# Placa_ADA.net
KiCad netlist of a schematic drawn in Altium Designer
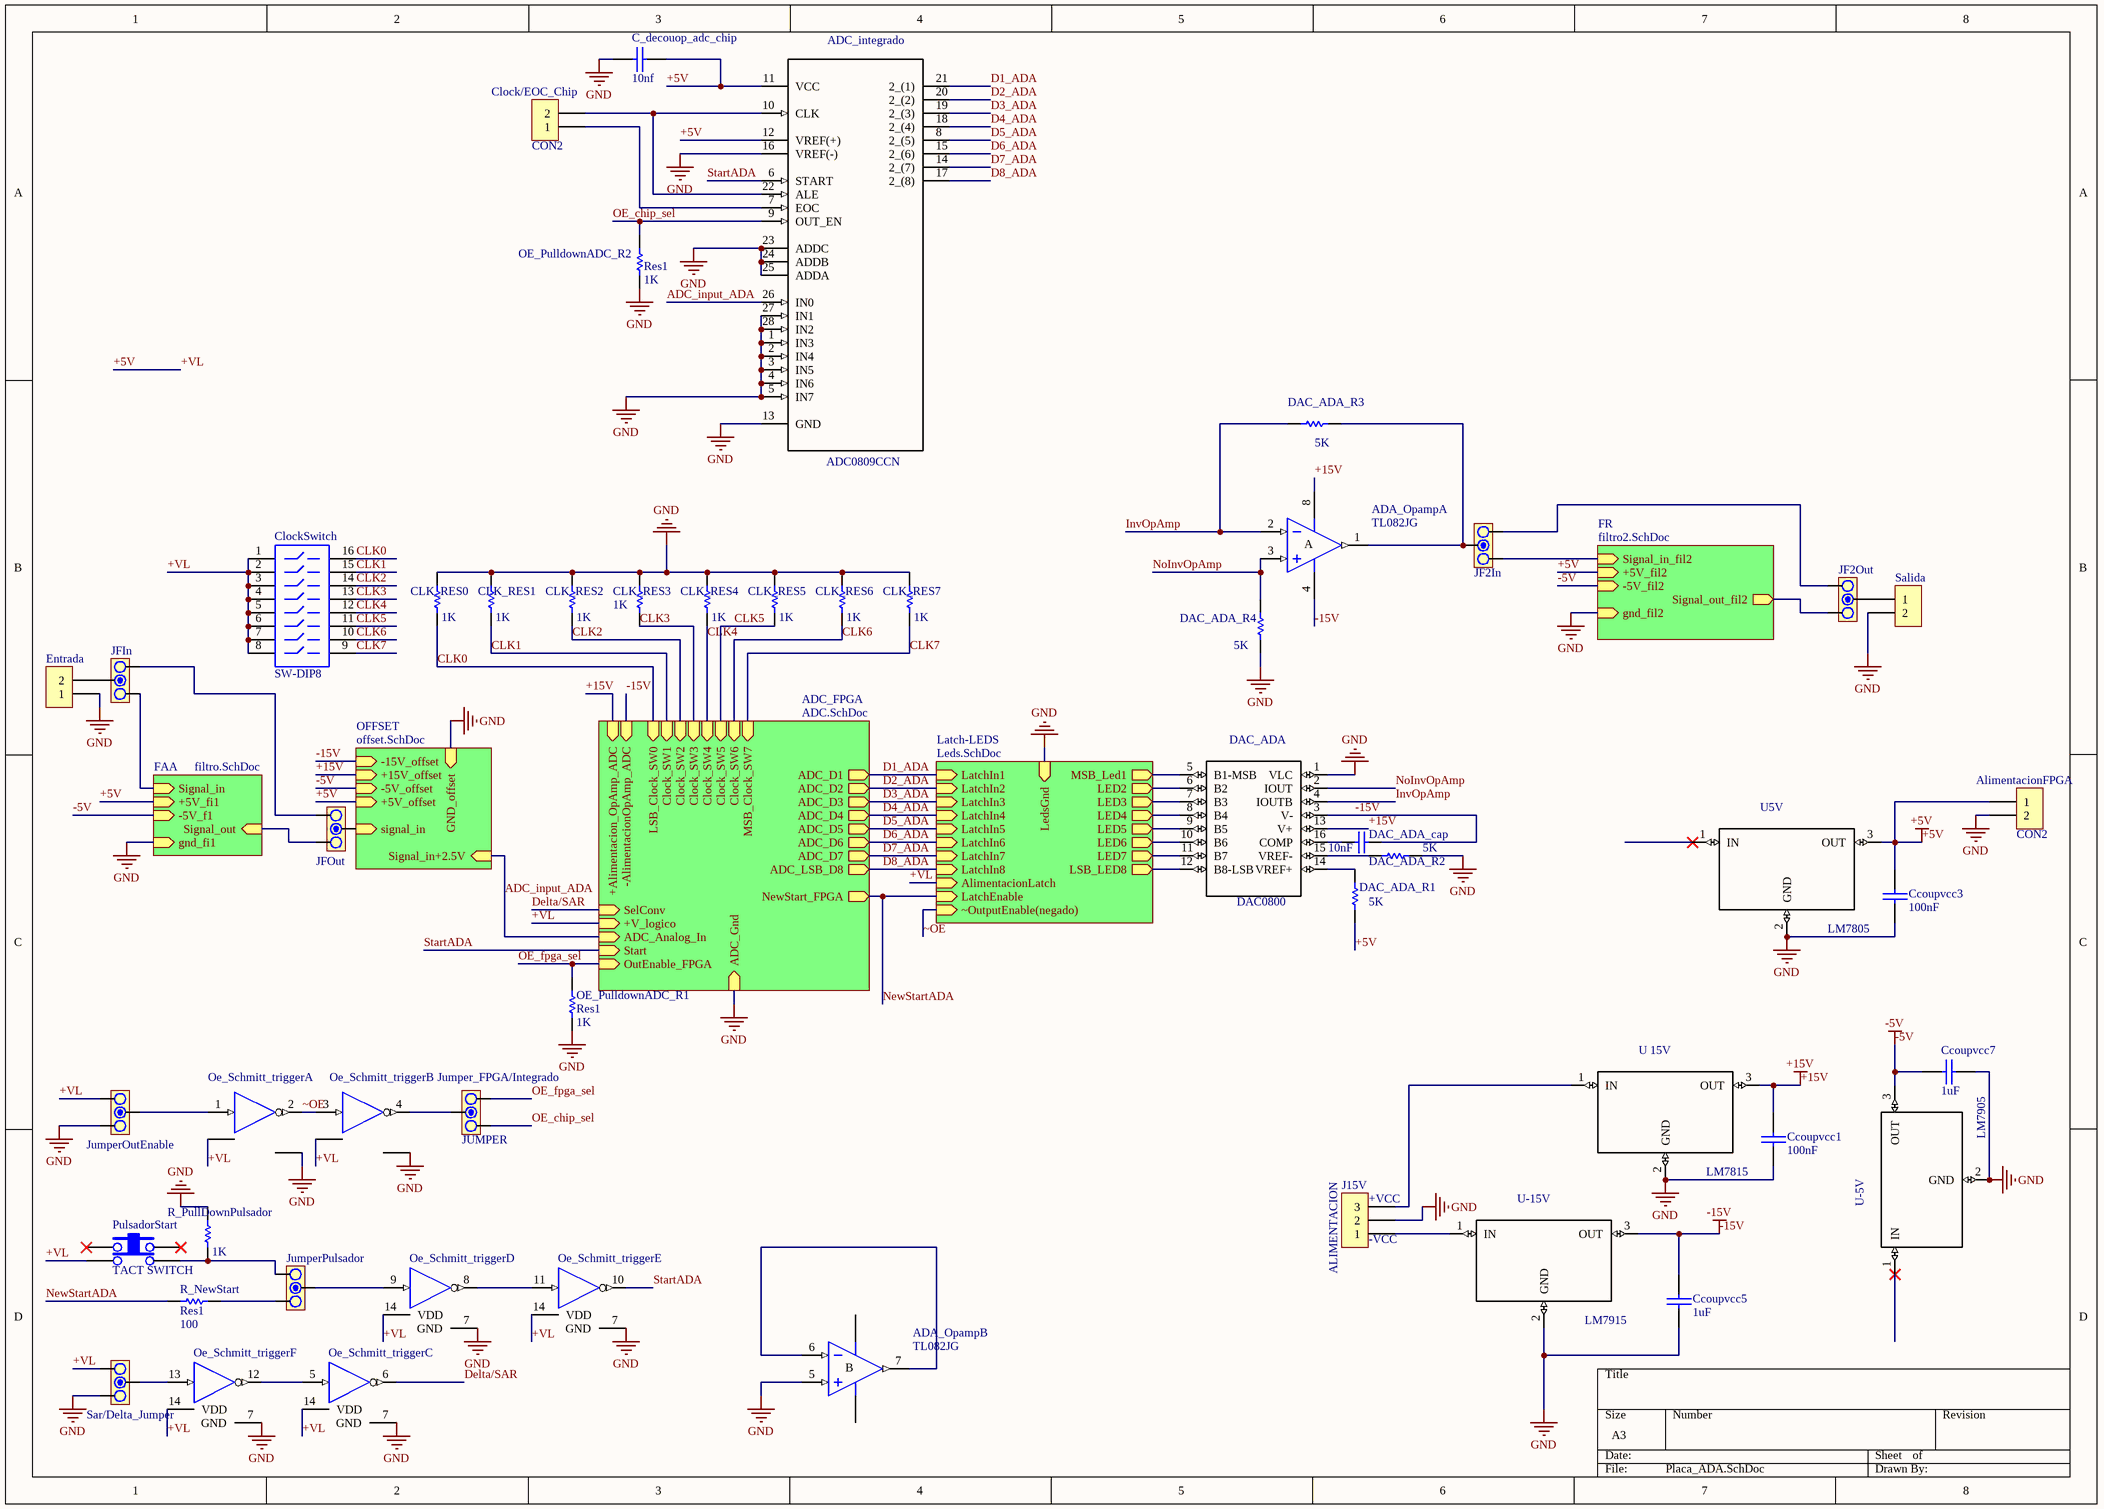
[diagram p0: Placa_ADA.SchDoc]

(export (version "E")
  (design (tool "Eeschema 10.0.6"))
  (components
    (comp (ref "ADA_Opamp")
      (value "TL082JG")
      (footprint "JG008")
      (description "JFET-Input Operational Amplifier")
      (fields (field (name "PUBLISHER") "Altium Limited"))
      (libsource (lib "TI Operational Amplifier") (part "TL082JG"))
    )
    (comp (ref "ADC_integrado")
      (value "ADC0809CCN")
      (footprint "*DIP254P1524X483-28")
      (description "8-bit Microprocessor Compatible A/D Converters With 8-Channel Multiplexer 28-PDIP -40 to 85")
      (fields (field (name "MP") "ADC0809CCN/NOPB") (field (name "MF") "Texas Instruments"))
      (libsource (lib "ADC0809CCN") (part "ADC0809CCN"))
    )
    (comp (ref "AlimentacionFPGA")
      (value "CON2")
      (footprint "SIP2")
      (libsource (lib "LIBEBAL") (part "CON2"))
    )
    (comp (ref "Ccoupvcc1") (value "100nF") (footprint "CAP200") (libsource (lib "LIBEBAL") (part "CAP")))
    (comp (ref "Ccoupvcc3") (value "100nF") (footprint "CAP200") (libsource (lib "LIBEBAL") (part "CAP")))
    (comp (ref "Ccoupvcc5") (value "1uF") (footprint "CAP200") (libsource (lib "LIBEBAL") (part "CAP")))
    (comp (ref "Ccoupvcc7") (value "1uF") (footprint "CAP200") (libsource (lib "LIBEBAL") (part "CAP")))
    (comp (ref "CLK_RES0")
      (value "1K")
      (footprint "AXIAL-0.3")
      (description "Resistor")
      (fields (field (name "Comment") "Res1") (field (name "PUBLISHER") "Altium Limited"))
      (libsource (lib "Miscellaneous Devices") (part "Res1"))
    )
    (comp (ref "CLK_RES1")
      (value "1K")
      (footprint "AXIAL-0.3")
      (description "Resistor")
      (fields (field (name "Comment") "Res1") (field (name "PUBLISHER") "Altium Limited"))
      (libsource (lib "Miscellaneous Devices") (part "Res1"))
    )
    (comp (ref "CLK_RES2")
      (value "1K")
      (footprint "AXIAL-0.3")
      (description "Resistor")
      (fields (field (name "Comment") "Res1") (field (name "PUBLISHER") "Altium Limited"))
      (libsource (lib "Miscellaneous Devices") (part "Res1"))
    )
    (comp (ref "CLK_RES3")
      (value "1K")
      (footprint "AXIAL-0.3")
      (description "Resistor")
      (fields (field (name "Comment") "Res1") (field (name "PUBLISHER") "Altium Limited"))
      (libsource (lib "Miscellaneous Devices") (part "Res1"))
    )
    (comp (ref "CLK_RES4")
      (value "1K")
      (footprint "AXIAL-0.3")
      (description "Resistor")
      (fields (field (name "Comment") "Res1") (field (name "PUBLISHER") "Altium Limited"))
      (libsource (lib "Miscellaneous Devices") (part "Res1"))
    )
    (comp (ref "CLK_RES5")
      (value "1K")
      (footprint "AXIAL-0.3")
      (description "Resistor")
      (fields (field (name "Comment") "Res1") (field (name "PUBLISHER") "Altium Limited"))
      (libsource (lib "Miscellaneous Devices") (part "Res1"))
    )
    (comp (ref "CLK_RES6")
      (value "1K")
      (footprint "AXIAL-0.3")
      (description "Resistor")
      (fields (field (name "Comment") "Res1") (field (name "PUBLISHER") "Altium Limited"))
      (libsource (lib "Miscellaneous Devices") (part "Res1"))
    )
    (comp (ref "CLK_RES7")
      (value "1K")
      (footprint "AXIAL-0.3")
      (description "Resistor")
      (fields (field (name "Comment") "Res1") (field (name "PUBLISHER") "Altium Limited"))
      (libsource (lib "Miscellaneous Devices") (part "Res1"))
    )
    (comp (ref "Clock/EOC_Chip") (value "CON2") (footprint "SIP2") (libsource (lib "") (part "CON2_1")))
    (comp (ref "ClockSwitch")
      (value "SW-DIP8")
      (footprint "DIP-16-KEY")
      (description "4009 Series DIP Switch, Raised actuator")
      (fields (field (name "PUBLISHER") "Altium Limited"))
      (libsource (lib "Miscellaneous Devices") (part "SW-DIP8"))
    )
    (comp (ref "C_decouop_adc_chip")
      (value "10nf")
      (footprint "CAP200")
      (libsource (lib "LIBEBAL") (part "CAP"))
    )
    (comp (ref "DAC_ADA")
      (value "DAC0800")
      (footprint "*DIL16")
      (fields
        (field (name "MF") "Texas Instruments")
        (field (name "DIGI-KEY_PART_NUMBER") "DAC0800LCN/NOPB-ND")
      )
      (libsource (lib "DAC0800") (part "DAC0800"))
    )
    (comp (ref "DAC_ADA_cap")
      (value "10nF")
      (footprint "RAD-0.3")
      (description "Capacitor")
      (fields (field (name "Comment") "Cap") (field (name "PUBLISHER") "Altium Limited"))
      (libsource (lib "Miscellaneous Devices") (part "Cap"))
    )
    (comp (ref "DAC_ADA_R1")
      (value "5K")
      (footprint "AXIAL-0.3")
      (description "Resistor")
      (fields (field (name "Comment") "Res1") (field (name "PUBLISHER") "Altium Limited"))
      (libsource (lib "Miscellaneous Devices") (part "Res1"))
    )
    (comp (ref "DAC_ADA_R2")
      (value "5K")
      (footprint "AXIAL-0.3")
      (description "Resistor")
      (fields (field (name "Comment") "Res1") (field (name "PUBLISHER") "Altium Limited"))
      (libsource (lib "Miscellaneous Devices") (part "Res1"))
    )
    (comp (ref "DAC_ADA_R3")
      (value "5K")
      (footprint "AXIAL-0.3")
      (description "Resistor")
      (fields (field (name "Comment") "Res1") (field (name "PUBLISHER") "Altium Limited"))
      (libsource (lib "Miscellaneous Devices") (part "Res1"))
    )
    (comp (ref "DAC_ADA_R4")
      (value "5K")
      (footprint "AXIAL-0.3")
      (description "Resistor")
      (fields (field (name "Comment") "Res1") (field (name "PUBLISHER") "Altium Limited"))
      (libsource (lib "Miscellaneous Devices") (part "Res1"))
    )
    (comp (ref "Entrada")
      (value "BORNERA 2")
      (footprint "BORNERA2")
      (libsource (lib "LIBEBAL") (part "BORNERA 2"))
    )
    (comp (ref "J15V")
      (value "ALIMENTACION")
      (footprint "BORNERA3")
      (libsource (lib "LIBEBAL") (part "BORNERA 3"))
    )
    (comp (ref "JF2In") (value "JUMPER") (footprint "JUMPER3") (libsource (lib "") (part "JUMPER3_1")))
    (comp (ref "JF2Out") (value "JUMPER") (footprint "JUMPER3") (libsource (lib "LIBEBAL") (part "JUMPER3")))
    (comp (ref "JFIn") (value "JUMPER") (footprint "JUMPER3") (libsource (lib "") (part "JUMPER3_1")))
    (comp (ref "JFOut") (value "JUMPER") (footprint "JUMPER3") (libsource (lib "LIBEBAL") (part "JUMPER3")))
    (comp (ref "JumperOutEnable")
      (value "JUMPER")
      (footprint "JUMPER3")
      (libsource (lib "LIBEBAL") (part "JUMPER3"))
    )
    (comp (ref "JumperPulsador")
      (value "JUMPER")
      (footprint "JUMPER3")
      (libsource (lib "LIBEBAL") (part "JUMPER3"))
    )
    (comp (ref "Jumper_FPGA/Integrado")
      (value "JUMPER")
      (footprint "JUMPER3")
      (libsource (lib "") (part "JUMPER3_1"))
    )
    (comp (ref "OE_PulldownADC_R1")
      (value "Res1")
      (footprint "AXIAL-0.3")
      (description "Resistor")
      (fields (field (name "ALTIUM_VALUE") "1K") (field (name "PUBLISHER") "Altium Limited"))
      (libsource (lib "Miscellaneous Devices") (part "Res1"))
    )
    (comp (ref "OE_PulldownADC_R2")
      (value "Res1")
      (footprint "AXIAL-0.3")
      (description "Resistor")
      (fields (field (name "ALTIUM_VALUE") "1K") (field (name "PUBLISHER") "Altium Limited"))
      (libsource (lib "Miscellaneous Devices") (part "Res1"))
    )
    (comp (ref "Oe_Schmitt_trigger")
      (value "MC74HC14AN")
      (footprint "646-06")
      (description "Hex Schmitt-Trigger Inverter")
      (fields (field (name "PUBLISHER") "Altium Limited"))
      (libsource (lib "ON Semi Logic Buffer Line Driver") (part "MC74HC14AN"))
    )
    (comp (ref "PulsadorStart")
      (value "TACT SWITCH")
      (footprint "TACTSWITCH")
      (libsource (lib "LIBEBAL") (part "TACT SWITCH"))
    )
    (comp (ref "R_NewStart")
      (value "Res1")
      (footprint "AXIAL-0.3")
      (description "Resistor")
      (fields (field (name "ALTIUM_VALUE") "100") (field (name "PUBLISHER") "Altium Limited"))
      (libsource (lib "Miscellaneous Devices") (part "Res1"))
    )
    (comp (ref "R_PullDownPulsador")
      (value "1K")
      (footprint "AXIAL-0.3")
      (description "Resistor")
      (fields (field (name "Comment") "Res1") (field (name "PUBLISHER") "Altium Limited"))
      (libsource (lib "Miscellaneous Devices") (part "Res1"))
    )
    (comp (ref "Salida") (value "BORNERA 2") (footprint "BORNERA2") (libsource (lib "") (part "BORNERA 2_1")))
    (comp (ref "Sar/Delta_Jumper")
      (value "JUMPER")
      (footprint "JUMPER3")
      (libsource (lib "LIBEBAL") (part "JUMPER3"))
    )
    (comp (ref "U 15V")
      (value "LM7815")
      (footprint "*TO220")
      (fields (field (name "MP") "LM7805") (field (name "MF") "Texas Instruments"))
      (libsource (lib "LM7805") (part "LM7805"))
    )
    (comp (ref "U-5V")
      (value "LM7905")
      (footprint "*TO220")
      (fields (field (name "MP") "LM7805") (field (name "MF") "Texas Instruments"))
      (libsource (lib "LM7805") (part "LM7805"))
    )
    (comp (ref "U-15V")
      (value "LM7915")
      (footprint "*TO220")
      (fields (field (name "MP") "LM7805") (field (name "MF") "Texas Instruments"))
      (libsource (lib "LM7805") (part "LM7805"))
    )
    (comp (ref "U5V")
      (value "LM7805")
      (footprint "*TO220")
      (fields (field (name "MF") "Texas Instruments"))
      (libsource (lib "LM7805") (part "LM7805"))
    )
  )
  (nets
    (net (code "1") (name "+5V") (class "Default")
      (node (ref "ADC_integrado") (pin "11") (pinfunction "VCC_11") (pintype "power_in"))
      (node (ref "ADC_integrado") (pin "12") (pinfunction "VREF(+)_12") (pintype "passive"))
      (node (ref "AlimentacionFPGA") (pin "1") (pinfunction "1_1") (pintype "passive"))
      (node (ref "C_decouop_adc_chip") (pin "2") (pinfunction "2_2") (pintype "passive"))
      (node (ref "Ccoupvcc3") (pin "1") (pinfunction "1_1") (pintype "passive"))
      (node (ref "ClockSwitch") (pin "1") (pinfunction "1_1") (pintype "passive"))
      (node (ref "ClockSwitch") (pin "2") (pinfunction "2_2") (pintype "passive"))
      (node (ref "ClockSwitch") (pin "3") (pinfunction "3_3") (pintype "passive"))
      (node (ref "ClockSwitch") (pin "4") (pinfunction "4_4") (pintype "passive"))
      (node (ref "ClockSwitch") (pin "5") (pinfunction "5_5") (pintype "passive"))
      (node (ref "ClockSwitch") (pin "6") (pinfunction "6_6") (pintype "passive"))
      (node (ref "ClockSwitch") (pin "7") (pinfunction "7_7") (pintype "passive"))
      (node (ref "ClockSwitch") (pin "8") (pinfunction "8_8") (pintype "passive"))
      (node (ref "DAC_ADA_R1") (pin "1") (pinfunction "1_1") (pintype "passive"))
      (node (ref "JumperOutEnable") (pin "3") (pinfunction "3_3") (pintype "passive"))
      (node (ref "Oe_Schmitt_trigger") (pin "14") (pinfunction "VDD_14") (pintype "power_in"))
      (node (ref "PulsadorStart") (pin "2") (pinfunction "2_2") (pintype "passive"))
      (node (ref "Sar/Delta_Jumper") (pin "3") (pinfunction "3_3") (pintype "passive"))
      (node (ref "U5V") (pin "3") (pinfunction "OUT_3") (pintype "bidirectional"))
    )
    (net (code "2") (name "+15V") (class "Default")
      (node (ref "ADA_Opamp") (pin "8") (pinfunction "V+_8") (pintype "power_in"))
      (node (ref "Ccoupvcc1") (pin "1") (pinfunction "1_1") (pintype "passive"))
      (node (ref "DAC_ADA") (pin "13") (pinfunction "V+_13") (pintype "bidirectional"))
      (node (ref "U 15V") (pin "3") (pinfunction "OUT_3") (pintype "bidirectional"))
    )
    (net (code "3") (name "-5V") (class "Default")
      (node (ref "Ccoupvcc7") (pin "1") (pinfunction "1_1") (pintype "passive"))
      (node (ref "U-5V") (pin "3") (pinfunction "OUT_3") (pintype "bidirectional"))
    )
    (net (code "4") (name "-15V") (class "Default")
      (node (ref "ADA_Opamp") (pin "4") (pinfunction "V-_4") (pintype "power_in"))
      (node (ref "Ccoupvcc5") (pin "1") (pinfunction "1_1") (pintype "passive"))
      (node (ref "DAC_ADA") (pin "3") (pinfunction "V-_3") (pintype "bidirectional"))
      (node (ref "DAC_ADA_cap") (pin "2") (pinfunction "2_2") (pintype "passive"))
      (node (ref "U-15V") (pin "3") (pinfunction "OUT_3") (pintype "bidirectional"))
    )
    (net (code "5") (name "/ADC_input_ADA") (class "Default")
      (node (ref "ADC_integrado") (pin "26") (pinfunction "IN0_26") (pintype "input"))
    )
    (net (code "6") (name "/CLK0") (class "Default")
      (node (ref "CLK_RES0") (pin "1") (pinfunction "1_1") (pintype "passive"))
      (node (ref "ClockSwitch") (pin "16") (pinfunction "16_16") (pintype "passive"))
    )
    (net (code "7") (name "/CLK1") (class "Default")
      (node (ref "CLK_RES1") (pin "1") (pinfunction "1_1") (pintype "passive"))
      (node (ref "ClockSwitch") (pin "15") (pinfunction "15_15") (pintype "passive"))
    )
    (net (code "8") (name "/CLK2") (class "Default")
      (node (ref "CLK_RES2") (pin "1") (pinfunction "1_1") (pintype "passive"))
      (node (ref "ClockSwitch") (pin "14") (pinfunction "14_14") (pintype "passive"))
    )
    (net (code "9") (name "/CLK3") (class "Default")
      (node (ref "CLK_RES3") (pin "1") (pinfunction "1_1") (pintype "passive"))
      (node (ref "ClockSwitch") (pin "13") (pinfunction "13_13") (pintype "passive"))
    )
    (net (code "10") (name "/CLK4") (class "Default")
      (node (ref "CLK_RES4") (pin "1") (pinfunction "1_1") (pintype "passive"))
      (node (ref "ClockSwitch") (pin "12") (pinfunction "12_12") (pintype "passive"))
    )
    (net (code "11") (name "/CLK5") (class "Default")
      (node (ref "CLK_RES5") (pin "1") (pinfunction "1_1") (pintype "passive"))
      (node (ref "ClockSwitch") (pin "11") (pinfunction "11_11") (pintype "passive"))
    )
    (net (code "12") (name "/CLK6") (class "Default")
      (node (ref "CLK_RES6") (pin "1") (pinfunction "1_1") (pintype "passive"))
      (node (ref "ClockSwitch") (pin "10") (pinfunction "10_10") (pintype "passive"))
    )
    (net (code "13") (name "/CLK7") (class "Default")
      (node (ref "CLK_RES7") (pin "1") (pinfunction "1_1") (pintype "passive"))
      (node (ref "ClockSwitch") (pin "9") (pinfunction "9_9") (pintype "passive"))
    )
    (net (code "14") (name "/D1_ADA") (class "Default")
      (node (ref "ADC_integrado") (pin "21") (pinfunction "2_(1)_21") (pintype "passive"))
    )
    (net (code "15") (name "/D2_ADA") (class "Default")
      (node (ref "ADC_integrado") (pin "20") (pinfunction "2_(2)_20") (pintype "passive"))
    )
    (net (code "16") (name "/D3_ADA") (class "Default")
      (node (ref "ADC_integrado") (pin "19") (pinfunction "2_(3)_19") (pintype "passive"))
    )
    (net (code "17") (name "/D4_ADA") (class "Default")
      (node (ref "ADC_integrado") (pin "18") (pinfunction "2_(4)_18") (pintype "passive"))
    )
    (net (code "18") (name "/D5_ADA") (class "Default")
      (node (ref "ADC_integrado") (pin "8") (pinfunction "2_(5)_8") (pintype "passive"))
    )
    (net (code "19") (name "/D6_ADA") (class "Default")
      (node (ref "ADC_integrado") (pin "15") (pinfunction "2_(6)_15") (pintype "passive"))
    )
    (net (code "20") (name "/D7_ADA") (class "Default")
      (node (ref "ADC_integrado") (pin "14") (pinfunction "2_(7)_14") (pintype "passive"))
    )
    (net (code "21") (name "/D8_ADA") (class "Default")
      (node (ref "ADC_integrado") (pin "17") (pinfunction "2_(8)_17") (pintype "passive"))
    )
    (net (code "22") (name "/Delta{slash}SAR") (class "Default")
      (node (ref "Oe_Schmitt_trigger") (pin "6") (pinfunction "~{OUT}_6") (pintype "output"))
    )
    (net (code "23") (name "/InvOpAmp") (class "Default")
      (node (ref "ADA_Opamp") (pin "2") (pinfunction "IN-_2") (pintype "input"))
      (node (ref "DAC_ADA") (pin "4") (pinfunction "IOUTB_4") (pintype "bidirectional"))
      (node (ref "DAC_ADA_R3") (pin "1") (pinfunction "1_1") (pintype "passive"))
    )
    (net (code "24") (name "/LED2") (class "Default")
      (node (ref "DAC_ADA") (pin "6") (pinfunction "B2_6") (pintype "bidirectional"))
    )
    (net (code "25") (name "/LED3") (class "Default")
      (node (ref "DAC_ADA") (pin "7") (pinfunction "B3_7") (pintype "bidirectional"))
    )
    (net (code "26") (name "/LED4") (class "Default")
      (node (ref "DAC_ADA") (pin "8") (pinfunction "B4_8") (pintype "bidirectional"))
    )
    (net (code "27") (name "/LED5") (class "Default")
      (node (ref "DAC_ADA") (pin "9") (pinfunction "B5_9") (pintype "bidirectional"))
    )
    (net (code "28") (name "/LED6") (class "Default")
      (node (ref "DAC_ADA") (pin "10") (pinfunction "B6_10") (pintype "bidirectional"))
    )
    (net (code "29") (name "/LED7") (class "Default")
      (node (ref "DAC_ADA") (pin "11") (pinfunction "B7_11") (pintype "bidirectional"))
    )
    (net (code "30") (name "/LSB_LED8") (class "Default")
      (node (ref "DAC_ADA") (pin "12") (pinfunction "B8-LSB_12") (pintype "bidirectional"))
    )
    (net (code "31") (name "/MSB_Led1") (class "Default")
      (node (ref "DAC_ADA") (pin "5") (pinfunction "B1-MSB_5") (pintype "bidirectional"))
    )
    (net (code "32") (name "/NewStartADA") (class "Default")
      (node (ref "R_NewStart") (pin "1") (pinfunction "1_1") (pintype "passive"))
    )
    (net (code "33") (name "/NoInvOpAmp") (class "Default")
      (node (ref "ADA_Opamp") (pin "3") (pinfunction "IN+_3") (pintype "input"))
      (node (ref "DAC_ADA") (pin "2") (pinfunction "IOUT_2") (pintype "bidirectional"))
      (node (ref "DAC_ADA_R4") (pin "2") (pinfunction "2_2") (pintype "passive"))
    )
    (net (code "34") (name "/OE_chip_sel") (class "Default")
      (node (ref "ADC_integrado") (pin "9") (pinfunction "OUT_EN_9") (pintype "input"))
      (node (ref "Jumper_FPGA/Integrado") (pin "3") (pinfunction "3_3") (pintype "passive"))
      (node (ref "OE_PulldownADC_R2") (pin "2") (pinfunction "2_2") (pintype "passive"))
    )
    (net (code "35") (name "/OE_fpga_sel") (class "Default")
      (node (ref "Jumper_FPGA/Integrado") (pin "1") (pinfunction "1_1") (pintype "passive"))
      (node (ref "OE_PulldownADC_R1") (pin "2") (pinfunction "2_2") (pintype "passive"))
    )
    (net (code "36") (name "/Signal_in") (class "Default")
      (node (ref "JFIn") (pin "3") (pinfunction "3_3") (pintype "passive"))
    )
    (net (code "37") (name "/Signal_in_fil2") (class "Default")
      (node (ref "JF2In") (pin "3") (pinfunction "3_3") (pintype "passive"))
    )
    (net (code "38") (name "/Signal_out") (class "Default")
      (node (ref "JFOut") (pin "1") (pinfunction "1_1") (pintype "passive"))
    )
    (net (code "39") (name "/Signal_out_fil2") (class "Default")
      (node (ref "JF2Out") (pin "1") (pinfunction "1_1") (pintype "passive"))
    )
    (net (code "40") (name "/StartADA") (class "Default")
      (node (ref "ADC_integrado") (pin "6") (pinfunction "START_6") (pintype "input"))
      (node (ref "Oe_Schmitt_trigger") (pin "10") (pinfunction "~{OUT}_10") (pintype "output"))
    )
    (net (code "41") (name "/signal_in") (class "Default")
      (node (ref "JFOut") (pin "2") (pinfunction "2_2") (pintype "passive"))
    )
    (net (code "42") (name "/~OE") (class "Default")
      (node (ref "Oe_Schmitt_trigger") (pin "2") (pinfunction "~{OUT}_2") (pintype "output"))
      (node (ref "Oe_Schmitt_trigger") (pin "3") (pinfunction "IN_3") (pintype "input"))
    )
    (net (code "43") (name "GND") (class "Default")
      (node (ref "ADA_Opamp") (pin "5") (pinfunction "IN+_5") (pintype "input"))
      (node (ref "ADC_integrado") (pin "1") (pinfunction "IN3_1") (pintype "input"))
      (node (ref "ADC_integrado") (pin "13") (pinfunction "GND_13") (pintype "passive"))
      (node (ref "ADC_integrado") (pin "16") (pinfunction "VREF(-)_16") (pintype "passive"))
      (node (ref "ADC_integrado") (pin "2") (pinfunction "IN4_2") (pintype "input"))
      (node (ref "ADC_integrado") (pin "23") (pinfunction "ADDC_23") (pintype "passive"))
      (node (ref "ADC_integrado") (pin "24") (pinfunction "ADDB_24") (pintype "passive"))
      (node (ref "ADC_integrado") (pin "25") (pinfunction "ADDA_25") (pintype "passive"))
      (node (ref "ADC_integrado") (pin "27") (pinfunction "IN1_27") (pintype "input"))
      (node (ref "ADC_integrado") (pin "28") (pinfunction "IN2_28") (pintype "input"))
      (node (ref "ADC_integrado") (pin "3") (pinfunction "IN5_3") (pintype "input"))
      (node (ref "ADC_integrado") (pin "4") (pinfunction "IN6_4") (pintype "input"))
      (node (ref "ADC_integrado") (pin "5") (pinfunction "IN7_5") (pintype "input"))
      (node (ref "AlimentacionFPGA") (pin "2") (pinfunction "2_2") (pintype "passive"))
      (node (ref "CLK_RES0") (pin "2") (pinfunction "2_2") (pintype "passive"))
      (node (ref "CLK_RES1") (pin "2") (pinfunction "2_2") (pintype "passive"))
      (node (ref "CLK_RES2") (pin "2") (pinfunction "2_2") (pintype "passive"))
      (node (ref "CLK_RES3") (pin "2") (pinfunction "2_2") (pintype "passive"))
      (node (ref "CLK_RES4") (pin "2") (pinfunction "2_2") (pintype "passive"))
      (node (ref "CLK_RES5") (pin "2") (pinfunction "2_2") (pintype "passive"))
      (node (ref "CLK_RES6") (pin "2") (pinfunction "2_2") (pintype "passive"))
      (node (ref "CLK_RES7") (pin "2") (pinfunction "2_2") (pintype "passive"))
      (node (ref "C_decouop_adc_chip") (pin "1") (pinfunction "1_1") (pintype "passive"))
      (node (ref "Ccoupvcc1") (pin "2") (pinfunction "2_2") (pintype "passive"))
      (node (ref "Ccoupvcc3") (pin "2") (pinfunction "2_2") (pintype "passive"))
      (node (ref "Ccoupvcc5") (pin "2") (pinfunction "2_2") (pintype "passive"))
      (node (ref "Ccoupvcc7") (pin "2") (pinfunction "2_2") (pintype "passive"))
      (node (ref "DAC_ADA") (pin "1") (pinfunction "VLC_1") (pintype "bidirectional"))
      (node (ref "DAC_ADA_R2") (pin "2") (pinfunction "2_2") (pintype "passive"))
      (node (ref "DAC_ADA_R4") (pin "1") (pinfunction "1_1") (pintype "passive"))
      (node (ref "Entrada") (pin "1") (pinfunction "1_1") (pintype "passive"))
      (node (ref "J15V") (pin "2") (pinfunction "2_2") (pintype "passive"))
      (node (ref "JumperOutEnable") (pin "1") (pinfunction "1_1") (pintype "passive"))
      (node (ref "OE_PulldownADC_R1") (pin "1") (pinfunction "1_1") (pintype "passive"))
      (node (ref "OE_PulldownADC_R2") (pin "1") (pinfunction "1_1") (pintype "passive"))
      (node (ref "Oe_Schmitt_trigger") (pin "7") (pinfunction "GND_7") (pintype "power_in"))
      (node (ref "R_PullDownPulsador") (pin "2") (pinfunction "2_2") (pintype "passive"))
      (node (ref "Salida") (pin "2") (pinfunction "2_2") (pintype "passive"))
      (node (ref "Sar/Delta_Jumper") (pin "1") (pinfunction "1_1") (pintype "passive"))
      (node (ref "U 15V") (pin "2") (pinfunction "GND_2") (pintype "bidirectional"))
      (node (ref "U-15V") (pin "2") (pinfunction "GND_2") (pintype "bidirectional"))
      (node (ref "U-5V") (pin "2") (pinfunction "GND_2") (pintype "bidirectional"))
      (node (ref "U5V") (pin "2") (pinfunction "GND_2") (pintype "bidirectional"))
    )
    (net (code "44") (name "Net-(ADA_OpampA-OUT)") (class "Default")
      (node (ref "ADA_Opamp") (pin "1") (pinfunction "OUT_1") (pintype "output"))
      (node (ref "DAC_ADA_R3") (pin "2") (pinfunction "2_2") (pintype "passive"))
      (node (ref "JF2In") (pin "2") (pinfunction "2_2") (pintype "passive"))
    )
    (net (code "45") (name "Net-(ADA_OpampB-IN-)") (class "Default")
      (node (ref "ADA_Opamp") (pin "6") (pinfunction "IN-_6") (pintype "input"))
      (node (ref "ADA_Opamp") (pin "7") (pinfunction "OUT_7") (pintype "output"))
    )
    (net (code "46") (name "Net-(ADC_integrado-ALE)") (class "Default")
      (node (ref "ADC_integrado") (pin "10") (pinfunction "CLK_10") (pintype "input"))
      (node (ref "ADC_integrado") (pin "22") (pinfunction "ALE_22") (pintype "input"))
      (node (ref "Clock/EOC_Chip") (pin "2") (pinfunction "2_2") (pintype "passive"))
    )
    (net (code "47") (name "Net-(ADC_integrado-EOC)") (class "Default")
      (node (ref "ADC_integrado") (pin "7") (pinfunction "EOC_7") (pintype "input"))
      (node (ref "Clock/EOC_Chip") (pin "1") (pinfunction "1_1") (pintype "passive"))
    )
    (net (code "48") (name "Net-(DAC_ADA-COMP)") (class "Default")
      (node (ref "DAC_ADA") (pin "16") (pinfunction "COMP_16") (pintype "bidirectional"))
      (node (ref "DAC_ADA_cap") (pin "1") (pinfunction "1_1") (pintype "passive"))
    )
    (net (code "49") (name "Net-(DAC_ADA-VREF+)") (class "Default")
      (node (ref "DAC_ADA") (pin "14") (pinfunction "VREF+_14") (pintype "bidirectional"))
      (node (ref "DAC_ADA_R1") (pin "2") (pinfunction "2_2") (pintype "passive"))
    )
    (net (code "50") (name "Net-(DAC_ADA-VREF-)") (class "Default")
      (node (ref "DAC_ADA") (pin "15") (pinfunction "VREF-_15") (pintype "bidirectional"))
      (node (ref "DAC_ADA_R2") (pin "1") (pinfunction "1_1") (pintype "passive"))
    )
    (net (code "51") (name "Net-(Entrada-Pad2)") (class "Default")
      (node (ref "Entrada") (pin "2") (pinfunction "2_2") (pintype "passive"))
      (node (ref "JFIn") (pin "2") (pinfunction "2_2") (pintype "passive"))
    )
    (net (code "52") (name "Net-(JF2In-Pad1)") (class "Default")
      (node (ref "JF2In") (pin "1") (pinfunction "1_1") (pintype "passive"))
      (node (ref "JF2Out") (pin "3") (pinfunction "3_3") (pintype "passive"))
    )
    (net (code "53") (name "Net-(JF2Out-Pad2)") (class "Default")
      (node (ref "JF2Out") (pin "2") (pinfunction "2_2") (pintype "passive"))
      (node (ref "Salida") (pin "1") (pinfunction "1_1") (pintype "passive"))
    )
    (net (code "54") (name "Net-(JFIn-Pad1)") (class "Default")
      (node (ref "JFIn") (pin "1") (pinfunction "1_1") (pintype "passive"))
      (node (ref "JFOut") (pin "3") (pinfunction "3_3") (pintype "passive"))
    )
    (net (code "55") (name "Net-(JumperPulsador-Pad1)") (class "Default")
      (node (ref "JumperPulsador") (pin "1") (pinfunction "1_1") (pintype "passive"))
      (node (ref "R_NewStart") (pin "2") (pinfunction "2_2") (pintype "passive"))
    )
    (net (code "56") (name "Net-(JumperPulsador-Pad3)") (class "Default")
      (node (ref "JumperPulsador") (pin "3") (pinfunction "3_3") (pintype "passive"))
      (node (ref "PulsadorStart") (pin "4") (pinfunction "4_4") (pintype "passive"))
      (node (ref "R_PullDownPulsador") (pin "1") (pinfunction "1_1") (pintype "passive"))
    )
    (net (code "57") (name "Net-(Oe_Schmitt_triggerA-IN)") (class "Default")
      (node (ref "JumperOutEnable") (pin "2") (pinfunction "2_2") (pintype "passive"))
      (node (ref "Oe_Schmitt_trigger") (pin "1") (pinfunction "IN_1") (pintype "input"))
    )
    (net (code "58") (name "Net-(Oe_Schmitt_triggerB-~{OUT})") (class "Default")
      (node (ref "Jumper_FPGA/Integrado") (pin "2") (pinfunction "2_2") (pintype "passive"))
      (node (ref "Oe_Schmitt_trigger") (pin "4") (pinfunction "~{OUT}_4") (pintype "output"))
    )
    (net (code "59") (name "Net-(Oe_Schmitt_triggerC-IN)") (class "Default")
      (node (ref "Oe_Schmitt_trigger") (pin "12") (pinfunction "~{OUT}_12") (pintype "output"))
      (node (ref "Oe_Schmitt_trigger") (pin "5") (pinfunction "IN_5") (pintype "input"))
    )
    (net (code "60") (name "Net-(Oe_Schmitt_triggerD-IN)") (class "Default")
      (node (ref "JumperPulsador") (pin "2") (pinfunction "2_2") (pintype "passive"))
      (node (ref "Oe_Schmitt_trigger") (pin "9") (pinfunction "IN_9") (pintype "input"))
    )
    (net (code "61") (name "Net-(Oe_Schmitt_triggerD-~{OUT})") (class "Default")
      (node (ref "Oe_Schmitt_trigger") (pin "11") (pinfunction "IN_11") (pintype "input"))
      (node (ref "Oe_Schmitt_trigger") (pin "8") (pinfunction "~{OUT}_8") (pintype "output"))
    )
    (net (code "62") (name "Net-(Oe_Schmitt_triggerF-IN)") (class "Default")
      (node (ref "Oe_Schmitt_trigger") (pin "13") (pinfunction "IN_13") (pintype "input"))
      (node (ref "Sar/Delta_Jumper") (pin "2") (pinfunction "2_2") (pintype "passive"))
    )
    (net (code "63") (name "Net-(U 15V-IN)") (class "Default")
      (node (ref "J15V") (pin "3") (pinfunction "3_3") (pintype "passive"))
      (node (ref "U 15V") (pin "1") (pinfunction "IN_1") (pintype "bidirectional"))
    )
    (net (code "64") (name "Net-(U-15V-IN)") (class "Default")
      (node (ref "J15V") (pin "1") (pinfunction "1_1") (pintype "passive"))
      (node (ref "U-15V") (pin "1") (pinfunction "IN_1") (pintype "bidirectional"))
    )
    (net (code "65") (name "unconnected-(ADA_OpampB-V+-Pad8)") (class "Default")
      (node (ref "ADA_Opamp") (pin "8") (pinfunction "V+_8") (pintype "power_in"))
    )
    (net (code "66") (name "unconnected-(ADA_OpampB-V--Pad4)") (class "Default")
      (node (ref "ADA_Opamp") (pin "4") (pinfunction "V-_4") (pintype "power_in"))
    )
    (net (code "67") (name "unconnected-(PulsadorStart-Pad1)") (class "Default")
      (node (ref "PulsadorStart") (pin "1") (pinfunction "1_1") (pintype "passive+no_connect"))
    )
    (net (code "68") (name "unconnected-(PulsadorStart-Pad3)") (class "Default")
      (node (ref "PulsadorStart") (pin "3") (pinfunction "3_3") (pintype "passive+no_connect"))
    )
    (net (code "69") (name "unconnected-(U-5V-IN-Pad1)") (class "Default")
      (node (ref "U-5V") (pin "1") (pinfunction "IN_1") (pintype "bidirectional+no_connect"))
    )
    (net (code "70") (name "unconnected-(U5V-IN-Pad1)") (class "Default")
      (node (ref "U5V") (pin "1") (pinfunction "IN_1") (pintype "bidirectional+no_connect"))
    )
  )
)
